# SAT_GPS_CLOCK_Input.net
KiCad netlist of a schematic drawn in Altium Designer
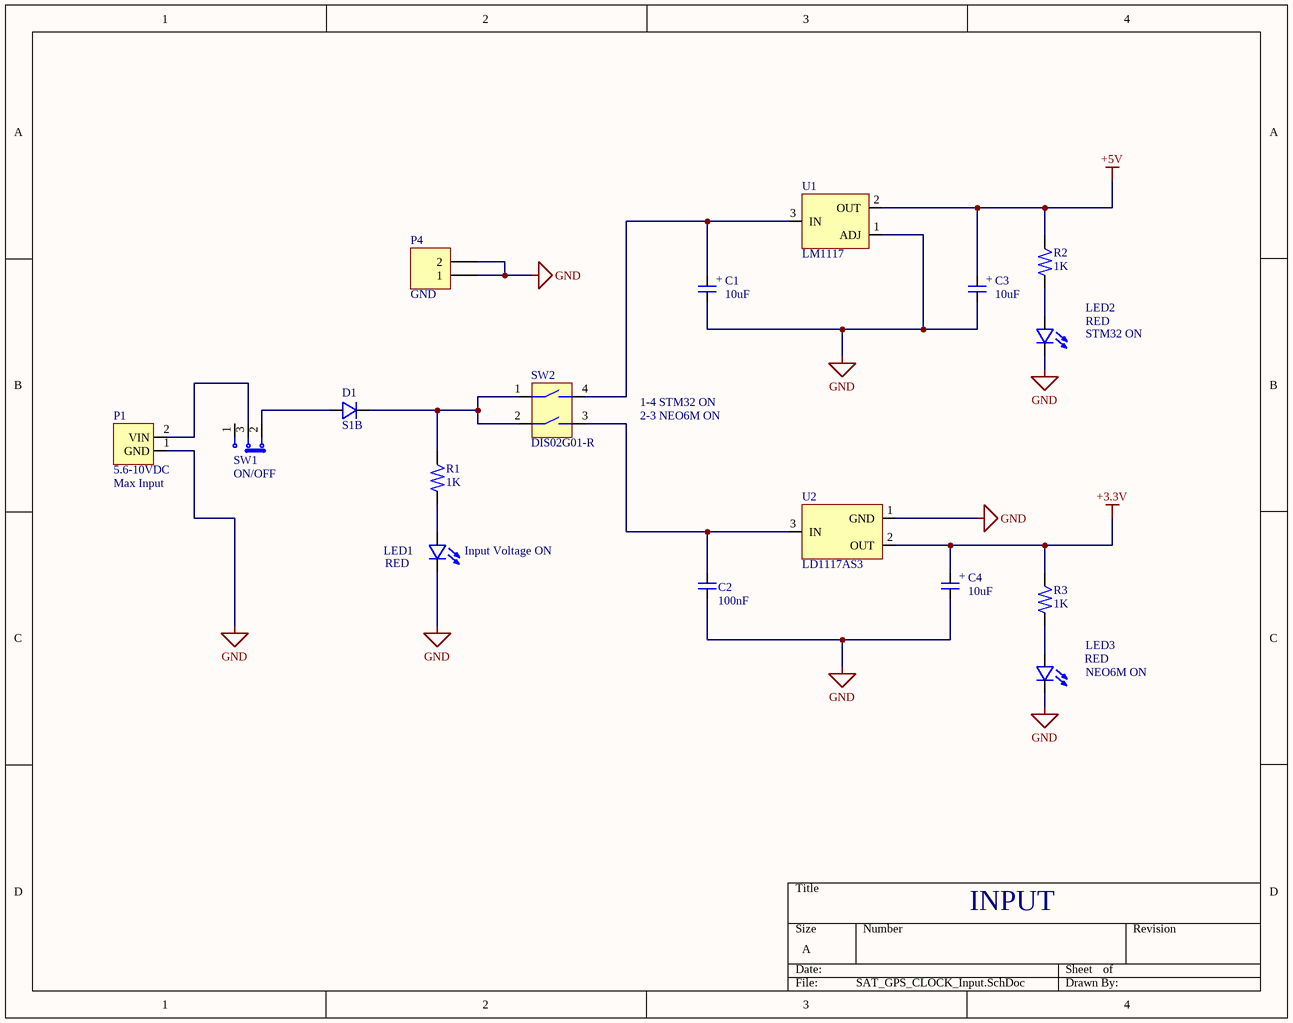
[diagram p0: SAT_GPS_CLOCK_Input.SchDoc]

(export (version "E")
  (design (tool "Eeschema 10.0.6"))
  (components
    (comp (ref "C1")
      (value "10uF")
      (footprint "SMT_CAP_EL_CHANG_VT1E100MC054000CE0")
      (description "SMT Capacitor Electrolytic 35V 10uF Pitch 1.3mm VT1E100MC054000CE0")
      (libsource (lib "SMT_CAP_EL_CHANG_VT1E100MC054000CE0") (part "SMT_CAP_EL_CHANG_VT1E100MC054000CE0"))
    )
    (comp (ref "C2")
      (value "100nF")
      (footprint "SMT_CAP_1206(3216)_SAMSUNG")
      (description "Ceramic Capacitor 1206(3216) Samsung CL31B104KBCNNNC 50VDC")
      (libsource (lib "SMT_CAP_1206(3216)_SAMSUNG") (part "SMT_CAP_1206(3216)_SAMSUNG"))
    )
    (comp (ref "C3")
      (value "10uF")
      (footprint "SMT_CAP_EL_CHANG_VT1E100MC054000CE0")
      (description "SMT Capacitor Electrolytic 35V 10uF Pitch 1.3mm VT1E100MC054000CE0")
      (libsource (lib "SMT_CAP_EL_CHANG_VT1E100MC054000CE0") (part "SMT_CAP_EL_CHANG_VT1E100MC054000CE0"))
    )
    (comp (ref "C4")
      (value "10uF")
      (footprint "SMT_CAP_EL_CHANG_VT1E100MC054000CE0")
      (description "SMT Capacitor Electrolytic 35V 10uF Pitch 1.3mm VT1E100MC054000CE0")
      (libsource (lib "SMT_CAP_EL_CHANG_VT1E100MC054000CE0") (part "SMT_CAP_EL_CHANG_VT1E100MC054000CE0"))
    )
    (comp (ref "D1")
      (value "S1B")
      (footprint "DIOM4227X23N")
      (description "Standart Diode DO-214AC 1A")
      (libsource (lib "SMT_DIODE_DO-214AC") (part "SMT_DIODE_DO-214AC"))
    )
    (comp (ref "LED1")
      (value "RED")
      (footprint "DIOM2012X18N")
      (description "Led Diode 0805(2012) Cathode Mark, 20mA")
      (libsource (lib "SMT_LED_0805(2012)") (part "SMT_LED_0805(2012)"))
    )
    (comp (ref "LED2")
      (value "RED")
      (footprint "DIOM2012X18N")
      (description "Led Diode 0805(2012) Cathode Mark, 20mA")
      (libsource (lib "SMT_LED_0805(2012)") (part "SMT_LED_0805(2012)"))
    )
    (comp (ref "LED3")
      (value "RED")
      (footprint "DIOM2012X18N")
      (description "Led Diode 0805(2012) Cathode Mark, 20mA")
      (libsource (lib "SMT_LED_0805(2012)") (part "SMT_LED_0805(2012)"))
    )
    (comp (ref "P1")
      (value "5.6-10VDC")
      (footprint "THT_CON_WAFER_2P_RIGHT-ANGLE_A2010WR0-2P-SW-5E")
      (description "Connector Wafer 2-Pins Pitch-2.0mm Right Angle A2010WR0-2P-SW-5E")
      (libsource (lib "THT_CON_WAFER_2P_RIGHT-ANGLE_A2010WR0-2P-SW-5E") (part "THT_CON_WAFER_2P_RIGHT-ANGLE_A2010WR0-2P-SW-5E"))
    )
    (comp (ref "P4")
      (value "GND")
      (footprint "HDR1X2")
      (description "Header, 2-Pin")
      (fields (field (name "PUBLISHER") "Altium Limited"))
      (libsource (lib "Miscellaneous Connectors") (part "Header 2"))
    )
    (comp (ref "R1")
      (value "1K")
      (footprint "SMT_RES_0805(2012)")
      (description "0805(2012) Resistor 1/4-1/8W 150V 2A")
      (libsource (lib "SMT_RES_0805(2012)") (part "SMT_RES_0805(2012)"))
    )
    (comp (ref "R2")
      (value "1K")
      (footprint "SMT_RES_0805(2012)")
      (description "0805(2012) Resistor 1/4-1/8W 150V 2A")
      (libsource (lib "SMT_RES_0805(2012)") (part "SMT_RES_0805(2012)"))
    )
    (comp (ref "R3")
      (value "1K")
      (footprint "SMT_RES_0805(2012)")
      (description "0805(2012) Resistor 1/4-1/8W 150V 2A")
      (libsource (lib "SMT_RES_0805(2012)") (part "SMT_RES_0805(2012)"))
    )
    (comp (ref "SW1")
      (value "ON/OFF")
      (footprint "THT_SSW_ESP1010")
      (description "Slide Switch ESP1010 12V 0.5A")
      (libsource (lib "THT_SSW_ESP1010") (part "THT_SSW_ESP1010"))
    )
    (comp (ref "SW2")
      (value "DIS02G01-R")
      (footprint "SMT_SWITCH_DIP_DIS02G01-R")
      (description "DIP SMD Switch 2-Line 4-Pole 2.54Pitch Rating 25mA/24Vdc Height 0.70mm")
      (libsource (lib "SMT_SWITCH_DIP_DIS02G01-R") (part "SMT_SWITCH_DIP_DIS02G01-R"))
    )
    (comp (ref "U1")
      (value "LM1117")
      (footprint "SOT230P700X180-4N")
      (description "LM1117 SOT-223 5V HTC Voltage Regulator")
      (libsource (lib "LM1117_SOT-223") (part "LM1117_SOT-223"))
    )
    (comp (ref "U2")
      (value "LD1117AS3")
      (footprint "SMT_VR_LD1117AS3")
      (description "Voltage Regulator ST LD1117AS33TR 1A 3.3V 10Vmax")
      (libsource (lib "SMT_VR_LD1117AS3") (part "SMT_VR_LD1117AS3"))
    )
  )
  (nets
    (net (code "1") (name "+3.3V") (class "Default")
      (node (ref "C4") (pin "1") (pinfunction "1_1") (pintype "passive"))
      (node (ref "R3") (pin "2") (pinfunction "2_2") (pintype "passive"))
      (node (ref "U2") (pin "2") (pinfunction "OUT_2") (pintype "passive"))
    )
    (net (code "2") (name "+5V") (class "Default")
      (node (ref "C3") (pin "1") (pinfunction "1_1") (pintype "passive"))
      (node (ref "R2") (pin "2") (pinfunction "2_2") (pintype "passive"))
      (node (ref "U1") (pin "2") (pinfunction "OUT_2") (pintype "passive"))
    )
    (net (code "3") (name "GND") (class "Default")
      (node (ref "C1") (pin "2") (pinfunction "2_2") (pintype "passive"))
      (node (ref "C2") (pin "1") (pinfunction "1_1") (pintype "passive"))
      (node (ref "C3") (pin "2") (pinfunction "2_2") (pintype "passive"))
      (node (ref "C4") (pin "2") (pinfunction "2_2") (pintype "passive"))
      (node (ref "LED1") (pin "2") (pinfunction "2_2") (pintype "passive"))
      (node (ref "LED2") (pin "2") (pinfunction "2_2") (pintype "passive"))
      (node (ref "LED3") (pin "2") (pinfunction "2_2") (pintype "passive"))
      (node (ref "P1") (pin "1") (pinfunction "GND_1") (pintype "passive"))
      (node (ref "P4") (pin "1") (pinfunction "1_1") (pintype "passive"))
      (node (ref "P4") (pin "2") (pinfunction "2_2") (pintype "passive"))
      (node (ref "U1") (pin "1") (pinfunction "ADJ_1") (pintype "passive"))
      (node (ref "U2") (pin "1") (pinfunction "GND_1") (pintype "passive"))
    )
    (net (code "4") (name "Net-(D1-Pad1)") (class "Default")
      (node (ref "D1") (pin "1") (pinfunction "1_1") (pintype "passive"))
      (node (ref "SW1") (pin "2") (pinfunction "2_2") (pintype "passive"))
    )
    (net (code "5") (name "Net-(D1-Pad2)") (class "Default")
      (node (ref "D1") (pin "2") (pinfunction "2_2") (pintype "passive"))
      (node (ref "R1") (pin "2") (pinfunction "2_2") (pintype "passive"))
      (node (ref "SW2") (pin "1") (pinfunction "1_1") (pintype "passive"))
      (node (ref "SW2") (pin "2") (pinfunction "2_2") (pintype "passive"))
    )
    (net (code "6") (name "Net-(LED1-Pad1)") (class "Default")
      (node (ref "LED1") (pin "1") (pinfunction "1_1") (pintype "passive"))
      (node (ref "R1") (pin "1") (pinfunction "1_1") (pintype "passive"))
    )
    (net (code "7") (name "Net-(LED2-Pad1)") (class "Default")
      (node (ref "LED2") (pin "1") (pinfunction "1_1") (pintype "passive"))
      (node (ref "R2") (pin "1") (pinfunction "1_1") (pintype "passive"))
    )
    (net (code "8") (name "Net-(LED3-Pad1)") (class "Default")
      (node (ref "LED3") (pin "1") (pinfunction "1_1") (pintype "passive"))
      (node (ref "R3") (pin "1") (pinfunction "1_1") (pintype "passive"))
    )
    (net (code "9") (name "Net-(P1-VIN)") (class "Default")
      (node (ref "P1") (pin "2") (pinfunction "VIN_2") (pintype "passive"))
      (node (ref "SW1") (pin "3") (pinfunction "3_3") (pintype "passive"))
    )
    (net (code "10") (name "Net-(U1-IN)") (class "Default")
      (node (ref "C1") (pin "1") (pinfunction "1_1") (pintype "passive"))
      (node (ref "SW2") (pin "4") (pinfunction "4_4") (pintype "passive"))
      (node (ref "U1") (pin "3") (pinfunction "IN_3") (pintype "passive"))
    )
    (net (code "11") (name "Net-(U2-IN)") (class "Default")
      (node (ref "C2") (pin "2") (pinfunction "2_2") (pintype "passive"))
      (node (ref "SW2") (pin "3") (pinfunction "3_3") (pintype "passive"))
      (node (ref "U2") (pin "3") (pinfunction "IN_3") (pintype "passive"))
    )
    (net (code "12") (name "unconnected-(SW1-Pad1)") (class "Default")
      (node (ref "SW1") (pin "1") (pinfunction "1_1") (pintype "passive"))
    )
  )
)
